# InterfaceBoardRevC.net
KiCad netlist of a schematic drawn in EAGLE
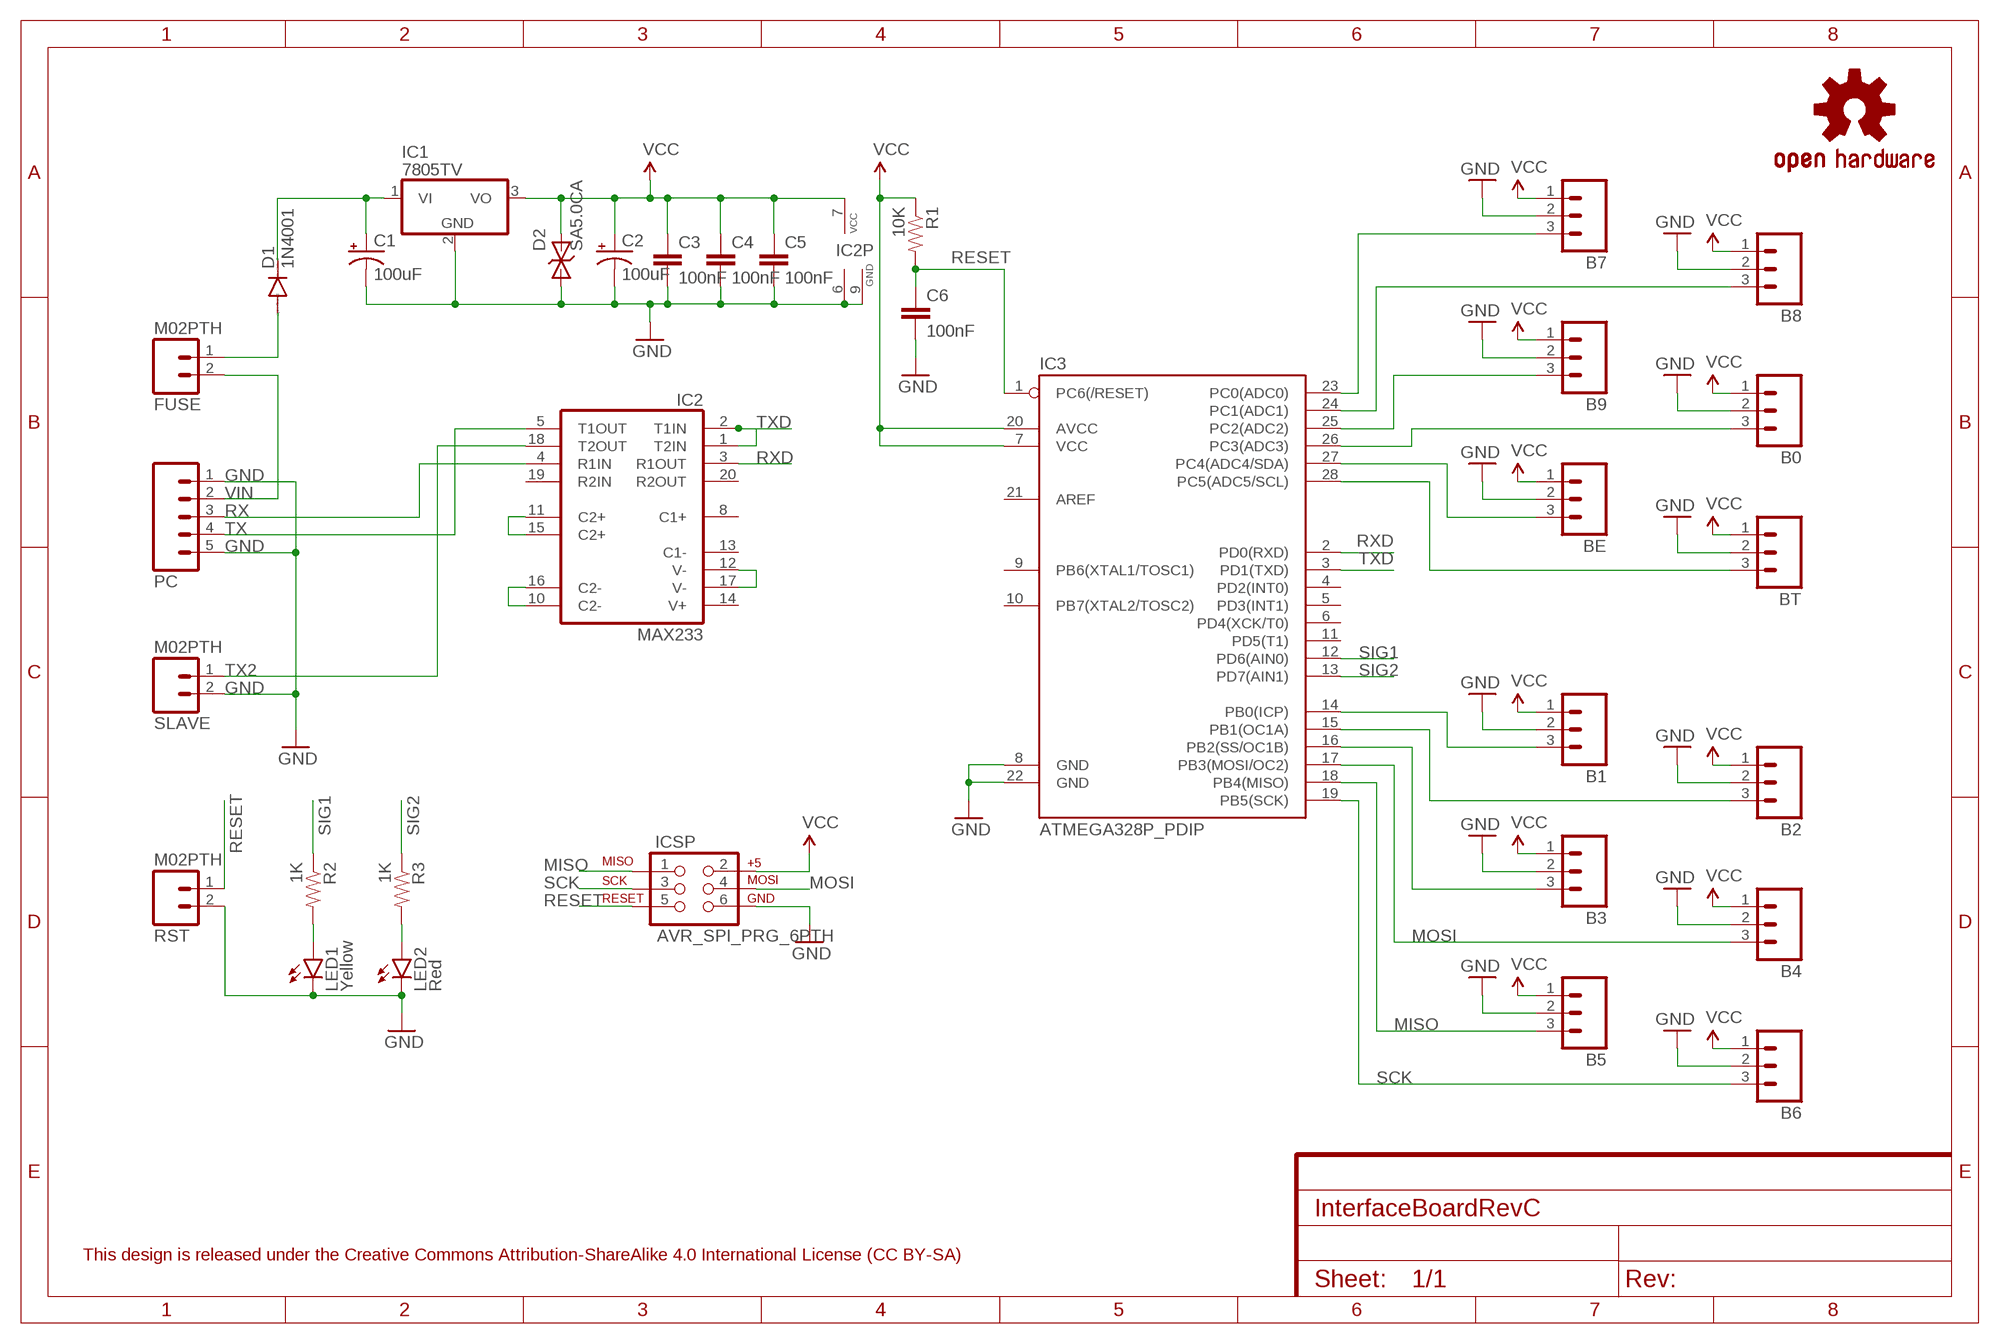
[diagram p0: schematic, sheet 1]

(export (version "E")
  (design (tool "Eeschema 10.0.6"))
  (components
    (comp (ref "B0")
      (value "M03PTH")
      (footprint "eagle-import:1X03")
      (libsource (lib "eagle-import") (part "M03PTH"))
    )
    (comp (ref "B1")
      (value "M03PTH")
      (footprint "eagle-import:1X03")
      (libsource (lib "eagle-import") (part "M03PTH"))
    )
    (comp (ref "B2")
      (value "M03PTH")
      (footprint "eagle-import:1X03")
      (libsource (lib "eagle-import") (part "M03PTH"))
    )
    (comp (ref "B3")
      (value "M03PTH")
      (footprint "eagle-import:1X03")
      (libsource (lib "eagle-import") (part "M03PTH"))
    )
    (comp (ref "B4")
      (value "M03PTH")
      (footprint "eagle-import:1X03")
      (libsource (lib "eagle-import") (part "M03PTH"))
    )
    (comp (ref "B5")
      (value "M03PTH")
      (footprint "eagle-import:1X03")
      (libsource (lib "eagle-import") (part "M03PTH"))
    )
    (comp (ref "B6")
      (value "M03PTH")
      (footprint "eagle-import:1X03")
      (libsource (lib "eagle-import") (part "M03PTH"))
    )
    (comp (ref "B7")
      (value "M03PTH")
      (footprint "eagle-import:1X03")
      (libsource (lib "eagle-import") (part "M03PTH"))
    )
    (comp (ref "B8")
      (value "M03PTH")
      (footprint "eagle-import:1X03")
      (libsource (lib "eagle-import") (part "M03PTH"))
    )
    (comp (ref "B9")
      (value "M03PTH")
      (footprint "eagle-import:1X03")
      (libsource (lib "eagle-import") (part "M03PTH"))
    )
    (comp (ref "BE")
      (value "M03PTH")
      (footprint "eagle-import:1X03")
      (libsource (lib "eagle-import") (part "M03PTH"))
    )
    (comp (ref "BT")
      (value "M03PTH")
      (footprint "eagle-import:1X03")
      (libsource (lib "eagle-import") (part "M03PTH"))
    )
    (comp (ref "C1")
      (value "100uF")
      (footprint "eagle-import:CPOL-RADIAL-100UF-25V")
      (libsource (lib "eagle-import") (part "CAP_POLPTH1"))
    )
    (comp (ref "C2")
      (value "100uF")
      (footprint "eagle-import:CPOL-RADIAL-100UF-25V")
      (libsource (lib "eagle-import") (part "CAP_POLPTH1"))
    )
    (comp (ref "C3")
      (value "100nF")
      (footprint "eagle-import:CAP-PTH-SMALL")
      (libsource (lib "eagle-import") (part "CAPPTH"))
    )
    (comp (ref "C4")
      (value "100nF")
      (footprint "eagle-import:CAP-PTH-SMALL")
      (libsource (lib "eagle-import") (part "CAPPTH"))
    )
    (comp (ref "C5")
      (value "100nF")
      (footprint "eagle-import:CAP-PTH-SMALL")
      (libsource (lib "eagle-import") (part "CAPPTH"))
    )
    (comp (ref "C6")
      (value "100nF")
      (footprint "eagle-import:CAP-PTH-SMALL")
      (libsource (lib "eagle-import") (part "CAPPTH"))
    )
    (comp (ref "D1")
      (value "1N4001")
      (footprint "eagle-import:DO41_DIODE")
      (libsource (lib "eagle-import") (part "1N4001"))
    )
    (comp (ref "D2")
      (value "SA5.0CA")
      (footprint "eagle-import:DO41_TVS")
      (libsource (lib "eagle-import") (part "SA5.0CA"))
    )
    (comp (ref "FUSE")
      (value "M02PTH")
      (footprint "eagle-import:1X02")
      (libsource (lib "eagle-import") (part "M02PTH"))
    )
    (comp (ref "IC1")
      (value "7805TV")
      (footprint "eagle-import:TO220V")
      (libsource (lib "eagle-import") (part "78TV05"))
    )
    (comp (ref "IC2")
      (value "MAX233")
      (footprint "eagle-import:DIL20")
      (fields (field (name "MPN") "MAX233ACPP+G36"))
      (libsource (lib "eagle-import") (part "MAX233"))
    )
    (comp (ref "IC3")
      (value "ATMEGA328P_PDIP")
      (footprint "eagle-import:DIL28-3")
      (libsource (lib "eagle-import") (part "ATMEGA328P_PDIP"))
    )
    (comp (ref "ICSP")
      (value "AVR_SPI_PRG_6PTH")
      (footprint "eagle-import:2X3")
      (libsource (lib "eagle-import") (part "AVR_SPI_PRG_6PTH"))
    )
    (comp (ref "LED1")
      (value "Yellow")
      (footprint "eagle-import:LED3MM_LARGEHOLES")
      (libsource (lib "eagle-import") (part "LED-LH3MM"))
    )
    (comp (ref "LED2")
      (value "Red")
      (footprint "eagle-import:LED3MM_LARGEHOLES")
      (libsource (lib "eagle-import") (part "LED-LH3MM"))
    )
    (comp (ref "LOGO1")
      (value "OSHW-LOGOS")
      (footprint "eagle-import:OSHW-LOGO-S")
      (libsource (lib "eagle-import") (part "OSHW-LOGOS"))
    )
    (comp (ref "PC")
      (value "M05PTH")
      (footprint "eagle-import:1X05")
      (libsource (lib "eagle-import") (part "M05PTH"))
    )
    (comp (ref "R1")
      (value "10K")
      (footprint "eagle-import:AXIAL-0.4")
      (libsource (lib "eagle-import") (part "RESISTORPTH-1/4W"))
    )
    (comp (ref "R2")
      (value "1K")
      (footprint "eagle-import:AXIAL-0.4")
      (libsource (lib "eagle-import") (part "RESISTORPTH-1/4W"))
    )
    (comp (ref "R3")
      (value "1K")
      (footprint "eagle-import:AXIAL-0.4")
      (libsource (lib "eagle-import") (part "RESISTORPTH-1/4W"))
    )
    (comp (ref "RST")
      (value "M02PTH")
      (footprint "eagle-import:1X02")
      (libsource (lib "eagle-import") (part "M02PTH"))
    )
    (comp (ref "SLAVE")
      (value "M02PTH")
      (footprint "eagle-import:1X02")
      (libsource (lib "eagle-import") (part "M02PTH"))
    )
  )
  (nets
    (net (code "1") (name "/MISO") (class "Default")
      (node (ref "B5") (pin "3") (pinfunction "3_3") (pintype "passive"))
      (node (ref "IC3") (pin "18") (pinfunction "PB4(MISO)_18") (pintype "bidirectional"))
      (node (ref "ICSP") (pin "1") (pinfunction "1_1") (pintype "passive"))
    )
    (net (code "2") (name "/MOSI") (class "Default")
      (node (ref "B4") (pin "3") (pinfunction "3_3") (pintype "passive"))
      (node (ref "IC3") (pin "17") (pinfunction "PB3(MOSI/OC2)_17") (pintype "bidirectional"))
      (node (ref "ICSP") (pin "4") (pinfunction "4_4") (pintype "passive"))
    )
    (net (code "3") (name "/RESET") (class "Default")
      (node (ref "C6") (pin "1") (pinfunction "1_1") (pintype "passive"))
      (node (ref "IC3") (pin "1") (pinfunction "PC6(/RESET)_1") (pintype "bidirectional"))
      (node (ref "ICSP") (pin "5") (pinfunction "5_5") (pintype "passive"))
      (node (ref "R1") (pin "P$2") (pinfunction "2_P$2") (pintype "passive"))
      (node (ref "RST") (pin "1") (pinfunction "1_1") (pintype "passive"))
    )
    (net (code "4") (name "/RX") (class "Default")
      (node (ref "IC2") (pin "4") (pinfunction "R1IN_4") (pintype "input"))
      (node (ref "PC") (pin "3") (pinfunction "3_3") (pintype "passive"))
    )
    (net (code "5") (name "/RXD") (class "Default")
      (node (ref "IC2") (pin "3") (pinfunction "R1OUT_3") (pintype "output"))
      (node (ref "IC3") (pin "2") (pinfunction "PD0(RXD)_2") (pintype "bidirectional"))
    )
    (net (code "6") (name "/SCK") (class "Default")
      (node (ref "B6") (pin "3") (pinfunction "3_3") (pintype "passive"))
      (node (ref "IC3") (pin "19") (pinfunction "PB5(SCK)_19") (pintype "bidirectional"))
      (node (ref "ICSP") (pin "3") (pinfunction "3_3") (pintype "passive"))
    )
    (net (code "7") (name "/SIG1") (class "Default")
      (node (ref "IC3") (pin "12") (pinfunction "PD6(AIN0)_12") (pintype "bidirectional"))
      (node (ref "R2") (pin "P$1") (pinfunction "1_P$1") (pintype "passive"))
    )
    (net (code "8") (name "/SIG2") (class "Default")
      (node (ref "IC3") (pin "13") (pinfunction "PD7(AIN1)_13") (pintype "bidirectional"))
      (node (ref "R3") (pin "P$1") (pinfunction "1_P$1") (pintype "passive"))
    )
    (net (code "9") (name "/TX") (class "Default")
      (node (ref "IC2") (pin "5") (pinfunction "T1OUT_5") (pintype "output"))
      (node (ref "PC") (pin "4") (pinfunction "4_4") (pintype "passive"))
    )
    (net (code "10") (name "/TX2") (class "Default")
      (node (ref "IC2") (pin "18") (pinfunction "T2OUT_18") (pintype "output"))
      (node (ref "SLAVE") (pin "1") (pinfunction "1_1") (pintype "passive"))
    )
    (net (code "11") (name "/TXD") (class "Default")
      (node (ref "IC2") (pin "1") (pinfunction "T2IN_1") (pintype "input"))
      (node (ref "IC2") (pin "2") (pinfunction "T1IN_2") (pintype "input"))
      (node (ref "IC3") (pin "3") (pinfunction "PD1(TXD)_3") (pintype "bidirectional"))
    )
    (net (code "12") (name "/VIN") (class "Default")
      (node (ref "FUSE") (pin "2") (pinfunction "2_2") (pintype "passive"))
      (node (ref "PC") (pin "2") (pinfunction "2_2") (pintype "passive"))
    )
    (net (code "13") (name "GND") (class "Default")
      (node (ref "B0") (pin "2") (pinfunction "2_2") (pintype "passive"))
      (node (ref "B1") (pin "2") (pinfunction "2_2") (pintype "passive"))
      (node (ref "B2") (pin "2") (pinfunction "2_2") (pintype "passive"))
      (node (ref "B3") (pin "2") (pinfunction "2_2") (pintype "passive"))
      (node (ref "B4") (pin "2") (pinfunction "2_2") (pintype "passive"))
      (node (ref "B5") (pin "2") (pinfunction "2_2") (pintype "passive"))
      (node (ref "B6") (pin "2") (pinfunction "2_2") (pintype "passive"))
      (node (ref "B7") (pin "2") (pinfunction "2_2") (pintype "passive"))
      (node (ref "B8") (pin "2") (pinfunction "2_2") (pintype "passive"))
      (node (ref "B9") (pin "2") (pinfunction "2_2") (pintype "passive"))
      (node (ref "BE") (pin "2") (pinfunction "2_2") (pintype "passive"))
      (node (ref "BT") (pin "2") (pinfunction "2_2") (pintype "passive"))
      (node (ref "C1") (pin "2") (pinfunction "-_2") (pintype "passive"))
      (node (ref "C2") (pin "2") (pinfunction "-_2") (pintype "passive"))
      (node (ref "C3") (pin "2") (pinfunction "2_2") (pintype "passive"))
      (node (ref "C4") (pin "2") (pinfunction "2_2") (pintype "passive"))
      (node (ref "C5") (pin "2") (pinfunction "2_2") (pintype "passive"))
      (node (ref "C6") (pin "2") (pinfunction "2_2") (pintype "passive"))
      (node (ref "D2") (pin "A") (pinfunction "A_A") (pintype "passive"))
      (node (ref "IC1") (pin "2") (pinfunction "GND_2") (pintype "passive"))
      (node (ref "IC2") (pin "6") (pinfunction "GND_6") (pintype "power_in"))
      (node (ref "IC2") (pin "9") (pinfunction "GND_9") (pintype "power_in"))
      (node (ref "IC3") (pin "22") (pinfunction "GND_22") (pintype "bidirectional"))
      (node (ref "IC3") (pin "8") (pinfunction "GND_8") (pintype "bidirectional"))
      (node (ref "ICSP") (pin "6") (pinfunction "6_6") (pintype "passive"))
      (node (ref "LED1") (pin "K") (pinfunction "C_K") (pintype "passive"))
      (node (ref "LED2") (pin "K") (pinfunction "C_K") (pintype "passive"))
      (node (ref "PC") (pin "1") (pinfunction "1_1") (pintype "passive"))
      (node (ref "PC") (pin "5") (pinfunction "5_5") (pintype "passive"))
      (node (ref "RST") (pin "2") (pinfunction "2_2") (pintype "passive"))
      (node (ref "SLAVE") (pin "2") (pinfunction "2_2") (pintype "passive"))
    )
    (net (code "14") (name "Net-(C1-+)") (class "Default")
      (node (ref "C1") (pin "1") (pinfunction "+_1") (pintype "passive"))
      (node (ref "D1") (pin "C") (pinfunction "C_C") (pintype "passive"))
      (node (ref "IC1") (pin "1") (pinfunction "VI_1") (pintype "input"))
    )
    (net (code "15") (name "Net-(D1-PadA)") (class "Default")
      (node (ref "D1") (pin "A") (pinfunction "A_A") (pintype "passive"))
      (node (ref "FUSE") (pin "1") (pinfunction "1_1") (pintype "passive"))
    )
    (net (code "16") (name "Net-(IC2A-C2+-Pad11)") (class "Default")
      (node (ref "IC2") (pin "11") (pinfunction "C2+_11") (pintype "bidirectional"))
      (node (ref "IC2") (pin "15") (pinfunction "C2+_15") (pintype "bidirectional"))
    )
    (net (code "17") (name "Net-(IC2A-C2--Pad10)") (class "Default")
      (node (ref "IC2") (pin "10") (pinfunction "C2-_10") (pintype "bidirectional"))
      (node (ref "IC2") (pin "16") (pinfunction "C2-_16") (pintype "bidirectional"))
    )
    (net (code "18") (name "Net-(IC2A-V--Pad12)") (class "Default")
      (node (ref "IC2") (pin "12") (pinfunction "V-_12") (pintype "bidirectional"))
      (node (ref "IC2") (pin "17") (pinfunction "V-_17") (pintype "bidirectional"))
    )
    (net (code "19") (name "Net-(IC3-PB0(ICP))") (class "Default")
      (node (ref "B1") (pin "3") (pinfunction "3_3") (pintype "passive"))
      (node (ref "IC3") (pin "14") (pinfunction "PB0(ICP)_14") (pintype "bidirectional"))
    )
    (net (code "20") (name "Net-(IC3-PB1(OC1A))") (class "Default")
      (node (ref "B2") (pin "3") (pinfunction "3_3") (pintype "passive"))
      (node (ref "IC3") (pin "15") (pinfunction "PB1(OC1A)_15") (pintype "bidirectional"))
    )
    (net (code "21") (name "Net-(IC3-PB2(SS{slash}OC1B))") (class "Default")
      (node (ref "B3") (pin "3") (pinfunction "3_3") (pintype "passive"))
      (node (ref "IC3") (pin "16") (pinfunction "PB2(SS/OC1B)_16") (pintype "bidirectional"))
    )
    (net (code "22") (name "Net-(IC3-PC0(ADC0))") (class "Default")
      (node (ref "B7") (pin "3") (pinfunction "3_3") (pintype "passive"))
      (node (ref "IC3") (pin "23") (pinfunction "PC0(ADC0)_23") (pintype "bidirectional"))
    )
    (net (code "23") (name "Net-(IC3-PC1(ADC1))") (class "Default")
      (node (ref "B8") (pin "3") (pinfunction "3_3") (pintype "passive"))
      (node (ref "IC3") (pin "24") (pinfunction "PC1(ADC1)_24") (pintype "bidirectional"))
    )
    (net (code "24") (name "Net-(IC3-PC2(ADC2))") (class "Default")
      (node (ref "B9") (pin "3") (pinfunction "3_3") (pintype "passive"))
      (node (ref "IC3") (pin "25") (pinfunction "PC2(ADC2)_25") (pintype "bidirectional"))
    )
    (net (code "25") (name "Net-(IC3-PC3(ADC3))") (class "Default")
      (node (ref "B0") (pin "3") (pinfunction "3_3") (pintype "passive"))
      (node (ref "IC3") (pin "26") (pinfunction "PC3(ADC3)_26") (pintype "bidirectional"))
    )
    (net (code "26") (name "Net-(IC3-PC4(ADC4{slash}SDA))") (class "Default")
      (node (ref "BE") (pin "3") (pinfunction "3_3") (pintype "passive"))
      (node (ref "IC3") (pin "27") (pinfunction "PC4(ADC4/SDA)_27") (pintype "bidirectional"))
    )
    (net (code "27") (name "Net-(IC3-PC5(ADC5{slash}SCL))") (class "Default")
      (node (ref "BT") (pin "3") (pinfunction "3_3") (pintype "passive"))
      (node (ref "IC3") (pin "28") (pinfunction "PC5(ADC5/SCL)_28") (pintype "bidirectional"))
    )
    (net (code "28") (name "Net-(R2-2)") (class "Default")
      (node (ref "LED1") (pin "A") (pinfunction "A_A") (pintype "passive"))
      (node (ref "R2") (pin "P$2") (pinfunction "2_P$2") (pintype "passive"))
    )
    (net (code "29") (name "Net-(R3-2)") (class "Default")
      (node (ref "LED2") (pin "A") (pinfunction "A_A") (pintype "passive"))
      (node (ref "R3") (pin "P$2") (pinfunction "2_P$2") (pintype "passive"))
    )
    (net (code "30") (name "VCC") (class "Default")
      (node (ref "B0") (pin "1") (pinfunction "1_1") (pintype "passive"))
      (node (ref "B1") (pin "1") (pinfunction "1_1") (pintype "passive"))
      (node (ref "B2") (pin "1") (pinfunction "1_1") (pintype "passive"))
      (node (ref "B3") (pin "1") (pinfunction "1_1") (pintype "passive"))
      (node (ref "B4") (pin "1") (pinfunction "1_1") (pintype "passive"))
      (node (ref "B5") (pin "1") (pinfunction "1_1") (pintype "passive"))
      (node (ref "B6") (pin "1") (pinfunction "1_1") (pintype "passive"))
      (node (ref "B7") (pin "1") (pinfunction "1_1") (pintype "passive"))
      (node (ref "B8") (pin "1") (pinfunction "1_1") (pintype "passive"))
      (node (ref "B9") (pin "1") (pinfunction "1_1") (pintype "passive"))
      (node (ref "BE") (pin "1") (pinfunction "1_1") (pintype "passive"))
      (node (ref "BT") (pin "1") (pinfunction "1_1") (pintype "passive"))
      (node (ref "C2") (pin "1") (pinfunction "+_1") (pintype "passive"))
      (node (ref "C3") (pin "1") (pinfunction "1_1") (pintype "passive"))
      (node (ref "C4") (pin "1") (pinfunction "1_1") (pintype "passive"))
      (node (ref "C5") (pin "1") (pinfunction "1_1") (pintype "passive"))
      (node (ref "D2") (pin "C") (pinfunction "C_C") (pintype "passive"))
      (node (ref "IC1") (pin "3") (pinfunction "VO_3") (pintype "passive"))
      (node (ref "IC2") (pin "7") (pinfunction "VCC_7") (pintype "power_in"))
      (node (ref "IC3") (pin "20") (pinfunction "AVCC_20") (pintype "bidirectional"))
      (node (ref "IC3") (pin "7") (pinfunction "VCC_7") (pintype "bidirectional"))
      (node (ref "ICSP") (pin "2") (pinfunction "2_2") (pintype "passive"))
      (node (ref "R1") (pin "P$1") (pinfunction "1_P$1") (pintype "passive"))
    )
    (net (code "31") (name "unconnected-(IC2A-C1+-Pad8)") (class "Default")
      (node (ref "IC2") (pin "8") (pinfunction "C1+_8") (pintype "bidirectional"))
    )
    (net (code "32") (name "unconnected-(IC2A-C1--Pad13)") (class "Default")
      (node (ref "IC2") (pin "13") (pinfunction "C1-_13") (pintype "bidirectional"))
    )
    (net (code "33") (name "unconnected-(IC2A-R2IN-Pad19)") (class "Default")
      (node (ref "IC2") (pin "19") (pinfunction "R2IN_19") (pintype "input"))
    )
    (net (code "34") (name "unconnected-(IC2A-R2OUT-Pad20)") (class "Default")
      (node (ref "IC2") (pin "20") (pinfunction "R2OUT_20") (pintype "output"))
    )
    (net (code "35") (name "unconnected-(IC2A-V+-Pad14)") (class "Default")
      (node (ref "IC2") (pin "14") (pinfunction "V+_14") (pintype "bidirectional"))
    )
    (net (code "36") (name "unconnected-(IC3-AREF-Pad21)") (class "Default")
      (node (ref "IC3") (pin "21") (pinfunction "AREF_21") (pintype "bidirectional"))
    )
    (net (code "37") (name "unconnected-(IC3-PB6(XTAL1{slash}TOSC1)-Pad9)") (class "Default")
      (node (ref "IC3") (pin "9") (pinfunction "PB6(XTAL1/TOSC1)_9") (pintype "bidirectional"))
    )
    (net (code "38") (name "unconnected-(IC3-PB7(XTAL2{slash}TOSC2)-Pad10)") (class "Default")
      (node (ref "IC3") (pin "10") (pinfunction "PB7(XTAL2/TOSC2)_10") (pintype "bidirectional"))
    )
    (net (code "39") (name "unconnected-(IC3-PD2(INT0)-Pad4)") (class "Default")
      (node (ref "IC3") (pin "4") (pinfunction "PD2(INT0)_4") (pintype "bidirectional"))
    )
    (net (code "40") (name "unconnected-(IC3-PD3(INT1)-Pad5)") (class "Default")
      (node (ref "IC3") (pin "5") (pinfunction "PD3(INT1)_5") (pintype "bidirectional"))
    )
    (net (code "41") (name "unconnected-(IC3-PD4(XCK{slash}T0)-Pad6)") (class "Default")
      (node (ref "IC3") (pin "6") (pinfunction "PD4(XCK/T0)_6") (pintype "bidirectional"))
    )
    (net (code "42") (name "unconnected-(IC3-PD5(T1)-Pad11)") (class "Default")
      (node (ref "IC3") (pin "11") (pinfunction "PD5(T1)_11") (pintype "bidirectional"))
    )
  )
)
